# circuitsalad.net
KiCad netlist of a schematic drawn in EAGLE
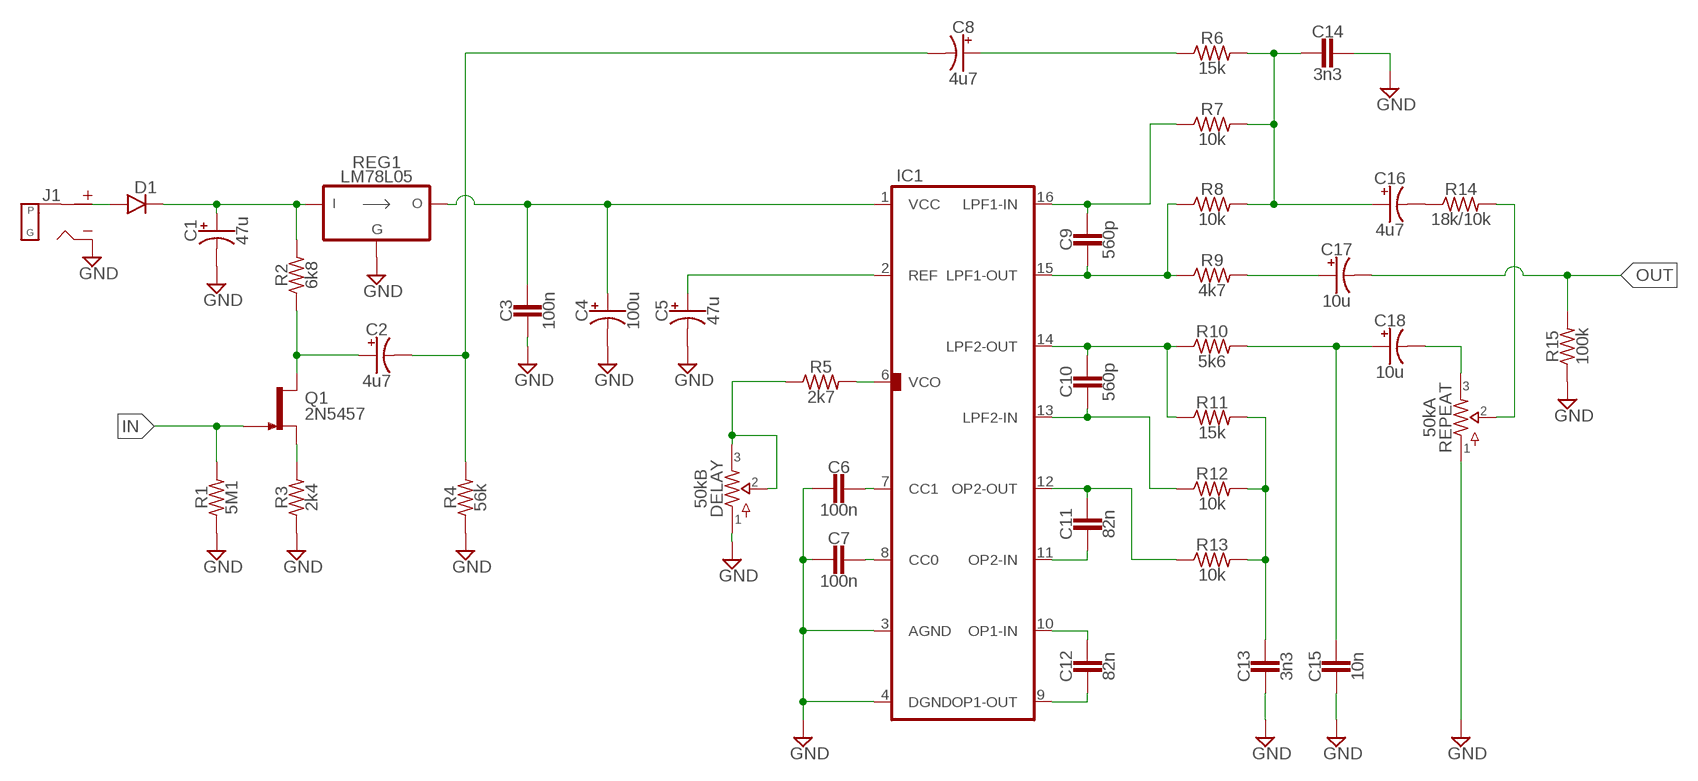
[diagram p0: schematic, sheet 1]

(export (version "E")
  (design (tool "Eeschema 10.0.6"))
  (components
    (comp (ref "C1")
      (value "47u")
      (footprint "eagle-import:050_020_1")
      (libsource (lib "eagle-import") (part "0501"))
    )
    (comp (ref "C2")
      (value "4u7")
      (footprint "eagle-import:050_020_1")
      (libsource (lib "eagle-import") (part "0501"))
    )
    (comp (ref "C3")
      (value "100n")
      (footprint "eagle-import:050X030_025_2")
      (libsource (lib "eagle-import") (part "CER/FILM2"))
    )
    (comp (ref "C4")
      (value "100u")
      (footprint "eagle-import:050_020_1")
      (libsource (lib "eagle-import") (part "0501"))
    )
    (comp (ref "C5")
      (value "47u")
      (footprint "eagle-import:050_020_1")
      (libsource (lib "eagle-import") (part "0501"))
    )
    (comp (ref "C6")
      (value "100n")
      (footprint "eagle-import:050X030_025_2")
      (libsource (lib "eagle-import") (part "CER/FILM2"))
    )
    (comp (ref "C7")
      (value "100n")
      (footprint "eagle-import:050X030_025_2")
      (libsource (lib "eagle-import") (part "CER/FILM2"))
    )
    (comp (ref "C8")
      (value "4u7")
      (footprint "eagle-import:050_020_1")
      (libsource (lib "eagle-import") (part "0501"))
    )
    (comp (ref "C9")
      (value "560p")
      (footprint "eagle-import:050X030_025_2")
      (libsource (lib "eagle-import") (part "CER/FILM2"))
    )
    (comp (ref "C10")
      (value "560p")
      (footprint "eagle-import:050X030_025_2")
      (libsource (lib "eagle-import") (part "CER/FILM2"))
    )
    (comp (ref "C11")
      (value "82n")
      (footprint "eagle-import:050X030_025_2")
      (libsource (lib "eagle-import") (part "CER/FILM2"))
    )
    (comp (ref "C12")
      (value "82n")
      (footprint "eagle-import:050X030_025_2")
      (libsource (lib "eagle-import") (part "CER/FILM2"))
    )
    (comp (ref "C13")
      (value "3n3")
      (footprint "eagle-import:050X030_025_2")
      (libsource (lib "eagle-import") (part "CER/FILM2"))
    )
    (comp (ref "C14")
      (value "3n3")
      (footprint "eagle-import:050X030_025_2")
      (libsource (lib "eagle-import") (part "CER/FILM2"))
    )
    (comp (ref "C15")
      (value "10n")
      (footprint "eagle-import:050X030_025_2")
      (libsource (lib "eagle-import") (part "CER/FILM2"))
    )
    (comp (ref "C16")
      (value "4u7")
      (footprint "eagle-import:050_020_1")
      (libsource (lib "eagle-import") (part "0501"))
    )
    (comp (ref "C17")
      (value "10u")
      (footprint "eagle-import:050_020_1")
      (libsource (lib "eagle-import") (part "0501"))
    )
    (comp (ref "C18")
      (value "10u")
      (footprint "eagle-import:050_020_1")
      (libsource (lib "eagle-import") (part "0501"))
    )
    (comp (ref "D1")
      (value "DO41.3")
      (footprint "eagle-import:DO41-3")
      (libsource (lib "eagle-import") (part "DO41.3"))
    )
    (comp (ref "DELAY")
      (value "50kB")
      (footprint "eagle-import:PADS_SMALL")
      (libsource (lib "eagle-import") (part "POTSSMALL_PADS"))
    )
    (comp (ref "IC1")
      (value "PT2399TH")
      (footprint "eagle-import:DIL16")
      (libsource (lib "eagle-import") (part "PT2399TH"))
    )
    (comp (ref "J1")
      (value "DC_MONO")
      (footprint "eagle-import:DC")
      (libsource (lib "eagle-import") (part "DC_MONO"))
    )
    (comp (ref "Q1")
      (value "2N5457")
      (footprint "eagle-import:TO92-")
      (libsource (lib "eagle-import") (part "2N5457"))
    )
    (comp (ref "R1")
      (value "5M1")
      (footprint "eagle-import:R0207_2V")
      (libsource (lib "eagle-import") (part "R_.2"))
    )
    (comp (ref "R2")
      (value "6k8")
      (footprint "eagle-import:R0207_2V")
      (libsource (lib "eagle-import") (part "R_.2"))
    )
    (comp (ref "R3")
      (value "2k4")
      (footprint "eagle-import:R0207_2V")
      (libsource (lib "eagle-import") (part "R_.2"))
    )
    (comp (ref "R4")
      (value "56k")
      (footprint "eagle-import:R0207_2V")
      (libsource (lib "eagle-import") (part "R_.2"))
    )
    (comp (ref "R5")
      (value "2k7")
      (footprint "eagle-import:R0207_2V")
      (libsource (lib "eagle-import") (part "R_.2"))
    )
    (comp (ref "R6")
      (value "15k")
      (footprint "eagle-import:R0207_2V")
      (libsource (lib "eagle-import") (part "R_.2"))
    )
    (comp (ref "R7")
      (value "10k")
      (footprint "eagle-import:R0207_2V")
      (libsource (lib "eagle-import") (part "R_.2"))
    )
    (comp (ref "R8")
      (value "10k")
      (footprint "eagle-import:R0207_2V")
      (libsource (lib "eagle-import") (part "R_.2"))
    )
    (comp (ref "R9")
      (value "4k7")
      (footprint "eagle-import:R0207_2V")
      (libsource (lib "eagle-import") (part "R_.2"))
    )
    (comp (ref "R10")
      (value "5k6")
      (footprint "eagle-import:R0207_2V")
      (libsource (lib "eagle-import") (part "R_.2"))
    )
    (comp (ref "R11")
      (value "15k")
      (footprint "eagle-import:R0207_2V")
      (libsource (lib "eagle-import") (part "R_.2"))
    )
    (comp (ref "R12")
      (value "10k")
      (footprint "eagle-import:R0207_2V")
      (libsource (lib "eagle-import") (part "R_.2"))
    )
    (comp (ref "R13")
      (value "10k")
      (footprint "eagle-import:R0207_2V")
      (libsource (lib "eagle-import") (part "R_.2"))
    )
    (comp (ref "R14")
      (value "18k/10k")
      (footprint "eagle-import:R0207_2V")
      (libsource (lib "eagle-import") (part "R_.2"))
    )
    (comp (ref "R15")
      (value "100k")
      (footprint "eagle-import:R0207_2V")
      (libsource (lib "eagle-import") (part "R_.2"))
    )
    (comp (ref "REG1")
      (value "LM78L05")
      (footprint "eagle-import:TO92-")
      (libsource (lib "eagle-import") (part "LM78L05"))
    )
    (comp (ref "REPEAT")
      (value "50kA")
      (footprint "eagle-import:PADS_SMALL")
      (libsource (lib "eagle-import") (part "POTSSMALL_PADS"))
    )
  )
  (nets
    (net (code "1") (name "GND") (class "Default")
      (node (ref "C1") (pin "-") (pinfunction "-_-") (pintype "passive"))
      (node (ref "C13") (pin "2") (pinfunction "2_2") (pintype "passive"))
      (node (ref "C14") (pin "1") (pinfunction "1_1") (pintype "passive"))
      (node (ref "C15") (pin "2") (pinfunction "2_2") (pintype "passive"))
      (node (ref "C3") (pin "2") (pinfunction "2_2") (pintype "passive"))
      (node (ref "C4") (pin "-") (pinfunction "-_-") (pintype "passive"))
      (node (ref "C5") (pin "-") (pinfunction "-_-") (pintype "passive"))
      (node (ref "C6") (pin "2") (pinfunction "2_2") (pintype "passive"))
      (node (ref "C7") (pin "2") (pinfunction "2_2") (pintype "passive"))
      (node (ref "DELAY") (pin "1") (pinfunction "1_1") (pintype "passive"))
      (node (ref "IC1") (pin "3") (pinfunction "AGND_3") (pintype "power_in"))
      (node (ref "IC1") (pin "4") (pinfunction "DGND_4") (pintype "power_in"))
      (node (ref "J1") (pin "S") (pinfunction "SLEEVE_S") (pintype "passive"))
      (node (ref "R1") (pin "1") (pinfunction "1_1") (pintype "passive"))
      (node (ref "R15") (pin "1") (pinfunction "1_1") (pintype "passive"))
      (node (ref "R3") (pin "1") (pinfunction "1_1") (pintype "passive"))
      (node (ref "R4") (pin "1") (pinfunction "1_1") (pintype "passive"))
      (node (ref "REG1") (pin "2") (pinfunction "GND_2") (pintype "passive"))
      (node (ref "REPEAT") (pin "1") (pinfunction "1_1") (pintype "passive"))
    )
    (net (code "2") (name "IN") (class "Default")
      (node (ref "Q1") (pin "1") (pinfunction "G_1") (pintype "passive"))
      (node (ref "R1") (pin "2") (pinfunction "2_2") (pintype "passive"))
    )
    (net (code "3") (name "Net-(C2-Pad-)") (class "Default")
      (node (ref "C2") (pin "-") (pinfunction "-_-") (pintype "passive"))
      (node (ref "C8") (pin "-") (pinfunction "-_-") (pintype "passive"))
      (node (ref "R4") (pin "2") (pinfunction "2_2") (pintype "passive"))
    )
    (net (code "4") (name "Net-(C8-Pad+)") (class "Default")
      (node (ref "C8") (pin "+") (pinfunction "+_+") (pintype "passive"))
      (node (ref "R6") (pin "1") (pinfunction "1_1") (pintype "passive"))
    )
    (net (code "5") (name "Net-(C13-Pad1)") (class "Default")
      (node (ref "C13") (pin "1") (pinfunction "1_1") (pintype "passive"))
      (node (ref "R11") (pin "2") (pinfunction "2_2") (pintype "passive"))
      (node (ref "R12") (pin "2") (pinfunction "2_2") (pintype "passive"))
      (node (ref "R13") (pin "2") (pinfunction "2_2") (pintype "passive"))
    )
    (net (code "6") (name "Net-(C14-Pad2)") (class "Default")
      (node (ref "C14") (pin "2") (pinfunction "2_2") (pintype "passive"))
      (node (ref "C16") (pin "+") (pinfunction "+_+") (pintype "passive"))
      (node (ref "R6") (pin "2") (pinfunction "2_2") (pintype "passive"))
      (node (ref "R7") (pin "2") (pinfunction "2_2") (pintype "passive"))
      (node (ref "R8") (pin "2") (pinfunction "2_2") (pintype "passive"))
    )
    (net (code "7") (name "Net-(C15-Pad1)") (class "Default")
      (node (ref "C15") (pin "1") (pinfunction "1_1") (pintype "passive"))
      (node (ref "C18") (pin "+") (pinfunction "+_+") (pintype "passive"))
      (node (ref "R10") (pin "2") (pinfunction "2_2") (pintype "passive"))
    )
    (net (code "8") (name "Net-(C16-Pad-)") (class "Default")
      (node (ref "C16") (pin "-") (pinfunction "-_-") (pintype "passive"))
      (node (ref "R14") (pin "1") (pinfunction "1_1") (pintype "passive"))
    )
    (net (code "9") (name "Net-(C17-Pad+)") (class "Default")
      (node (ref "C17") (pin "+") (pinfunction "+_+") (pintype "passive"))
      (node (ref "R9") (pin "2") (pinfunction "2_2") (pintype "passive"))
    )
    (net (code "10") (name "Net-(C18-Pad-)") (class "Default")
      (node (ref "C18") (pin "-") (pinfunction "-_-") (pintype "passive"))
      (node (ref "REPEAT") (pin "3") (pinfunction "3_3") (pintype "passive"))
    )
    (net (code "11") (name "Net-(DELAY-Pad2)") (class "Default")
      (node (ref "DELAY") (pin "2") (pinfunction "2_2") (pintype "passive"))
      (node (ref "DELAY") (pin "3") (pinfunction "3_3") (pintype "passive"))
      (node (ref "R5") (pin "1") (pinfunction "1_1") (pintype "passive"))
    )
    (net (code "12") (name "Net-(IC1-CC0)") (class "Default")
      (node (ref "C7") (pin "1") (pinfunction "1_1") (pintype "passive"))
      (node (ref "IC1") (pin "8") (pinfunction "CC0_8") (pintype "input"))
    )
    (net (code "13") (name "Net-(IC1-CC1)") (class "Default")
      (node (ref "C6") (pin "1") (pinfunction "1_1") (pintype "passive"))
      (node (ref "IC1") (pin "7") (pinfunction "CC1_7") (pintype "input"))
    )
    (net (code "14") (name "Net-(IC1-LPF1-IN)") (class "Default")
      (node (ref "C9") (pin "1") (pinfunction "1_1") (pintype "passive"))
      (node (ref "IC1") (pin "16") (pinfunction "LPF1-IN_16") (pintype "input"))
      (node (ref "R7") (pin "1") (pinfunction "1_1") (pintype "passive"))
    )
    (net (code "15") (name "Net-(IC1-LPF1-OUT)") (class "Default")
      (node (ref "C9") (pin "2") (pinfunction "2_2") (pintype "passive"))
      (node (ref "IC1") (pin "15") (pinfunction "LPF1-OUT_15") (pintype "output"))
      (node (ref "R8") (pin "1") (pinfunction "1_1") (pintype "passive"))
      (node (ref "R9") (pin "1") (pinfunction "1_1") (pintype "passive"))
    )
    (net (code "16") (name "Net-(IC1-LPF2-IN)") (class "Default")
      (node (ref "C10") (pin "2") (pinfunction "2_2") (pintype "passive"))
      (node (ref "IC1") (pin "13") (pinfunction "LPF2-IN_13") (pintype "input"))
      (node (ref "R12") (pin "1") (pinfunction "1_1") (pintype "passive"))
    )
    (net (code "17") (name "Net-(IC1-LPF2-OUT)") (class "Default")
      (node (ref "C10") (pin "1") (pinfunction "1_1") (pintype "passive"))
      (node (ref "IC1") (pin "14") (pinfunction "LPF2-OUT_14") (pintype "output"))
      (node (ref "R10") (pin "1") (pinfunction "1_1") (pintype "passive"))
      (node (ref "R11") (pin "1") (pinfunction "1_1") (pintype "passive"))
    )
    (net (code "18") (name "Net-(IC1-OP1-IN)") (class "Default")
      (node (ref "C12") (pin "1") (pinfunction "1_1") (pintype "passive"))
      (node (ref "IC1") (pin "10") (pinfunction "OP1-IN_10") (pintype "input"))
    )
    (net (code "19") (name "Net-(IC1-OP1-OUT)") (class "Default")
      (node (ref "C12") (pin "2") (pinfunction "2_2") (pintype "passive"))
      (node (ref "IC1") (pin "9") (pinfunction "OP1-OUT_9") (pintype "output"))
    )
    (net (code "20") (name "Net-(IC1-OP2-IN)") (class "Default")
      (node (ref "C11") (pin "2") (pinfunction "2_2") (pintype "passive"))
      (node (ref "IC1") (pin "11") (pinfunction "OP2-IN_11") (pintype "input"))
    )
    (net (code "21") (name "Net-(IC1-OP2-OUT)") (class "Default")
      (node (ref "C11") (pin "1") (pinfunction "1_1") (pintype "passive"))
      (node (ref "IC1") (pin "12") (pinfunction "OP2-OUT_12") (pintype "output"))
      (node (ref "R13") (pin "1") (pinfunction "1_1") (pintype "passive"))
    )
    (net (code "22") (name "Net-(IC1-REF)") (class "Default")
      (node (ref "C5") (pin "+") (pinfunction "+_+") (pintype "passive"))
      (node (ref "IC1") (pin "2") (pinfunction "REF_2") (pintype "input"))
    )
    (net (code "23") (name "Net-(IC1-VCC)") (class "Default")
      (node (ref "C3") (pin "1") (pinfunction "1_1") (pintype "passive"))
      (node (ref "C4") (pin "+") (pinfunction "+_+") (pintype "passive"))
      (node (ref "IC1") (pin "1") (pinfunction "VCC_1") (pintype "power_in"))
      (node (ref "REG1") (pin "3") (pinfunction "VO_3") (pintype "passive"))
    )
    (net (code "24") (name "Net-(IC1-VCO)") (class "Default")
      (node (ref "IC1") (pin "6") (pinfunction "VCO_6") (pintype "input"))
      (node (ref "R5") (pin "2") (pinfunction "2_2") (pintype "passive"))
    )
    (net (code "25") (name "Net-(J1-TIP)") (class "Default")
      (node (ref "D1") (pin "A") (pinfunction "A_A") (pintype "passive"))
      (node (ref "J1") (pin "T") (pinfunction "TIP_T") (pintype "passive"))
    )
    (net (code "26") (name "Net-(Q1-D)") (class "Default")
      (node (ref "C2") (pin "+") (pinfunction "+_+") (pintype "passive"))
      (node (ref "Q1") (pin "3") (pinfunction "D_3") (pintype "passive"))
      (node (ref "R2") (pin "1") (pinfunction "1_1") (pintype "passive"))
    )
    (net (code "27") (name "Net-(Q1-S)") (class "Default")
      (node (ref "Q1") (pin "2") (pinfunction "S_2") (pintype "passive"))
      (node (ref "R3") (pin "2") (pinfunction "2_2") (pintype "passive"))
    )
    (net (code "28") (name "Net-(R14-Pad2)") (class "Default")
      (node (ref "R14") (pin "2") (pinfunction "2_2") (pintype "passive"))
      (node (ref "REPEAT") (pin "2") (pinfunction "2_2") (pintype "passive"))
    )
    (net (code "29") (name "Net-(REG1-VI)") (class "Default")
      (node (ref "C1") (pin "+") (pinfunction "+_+") (pintype "passive"))
      (node (ref "D1") (pin "C") (pinfunction "C_C") (pintype "passive"))
      (node (ref "R2") (pin "2") (pinfunction "2_2") (pintype "passive"))
      (node (ref "REG1") (pin "1") (pinfunction "VI_1") (pintype "input"))
    )
    (net (code "30") (name "OUT") (class "Default")
      (node (ref "C17") (pin "-") (pinfunction "-_-") (pintype "passive"))
      (node (ref "R15") (pin "2") (pinfunction "2_2") (pintype "passive"))
    )
  )
)
